# Robonaut2.net
KiCad netlist of a schematic drawn in Altium Designer
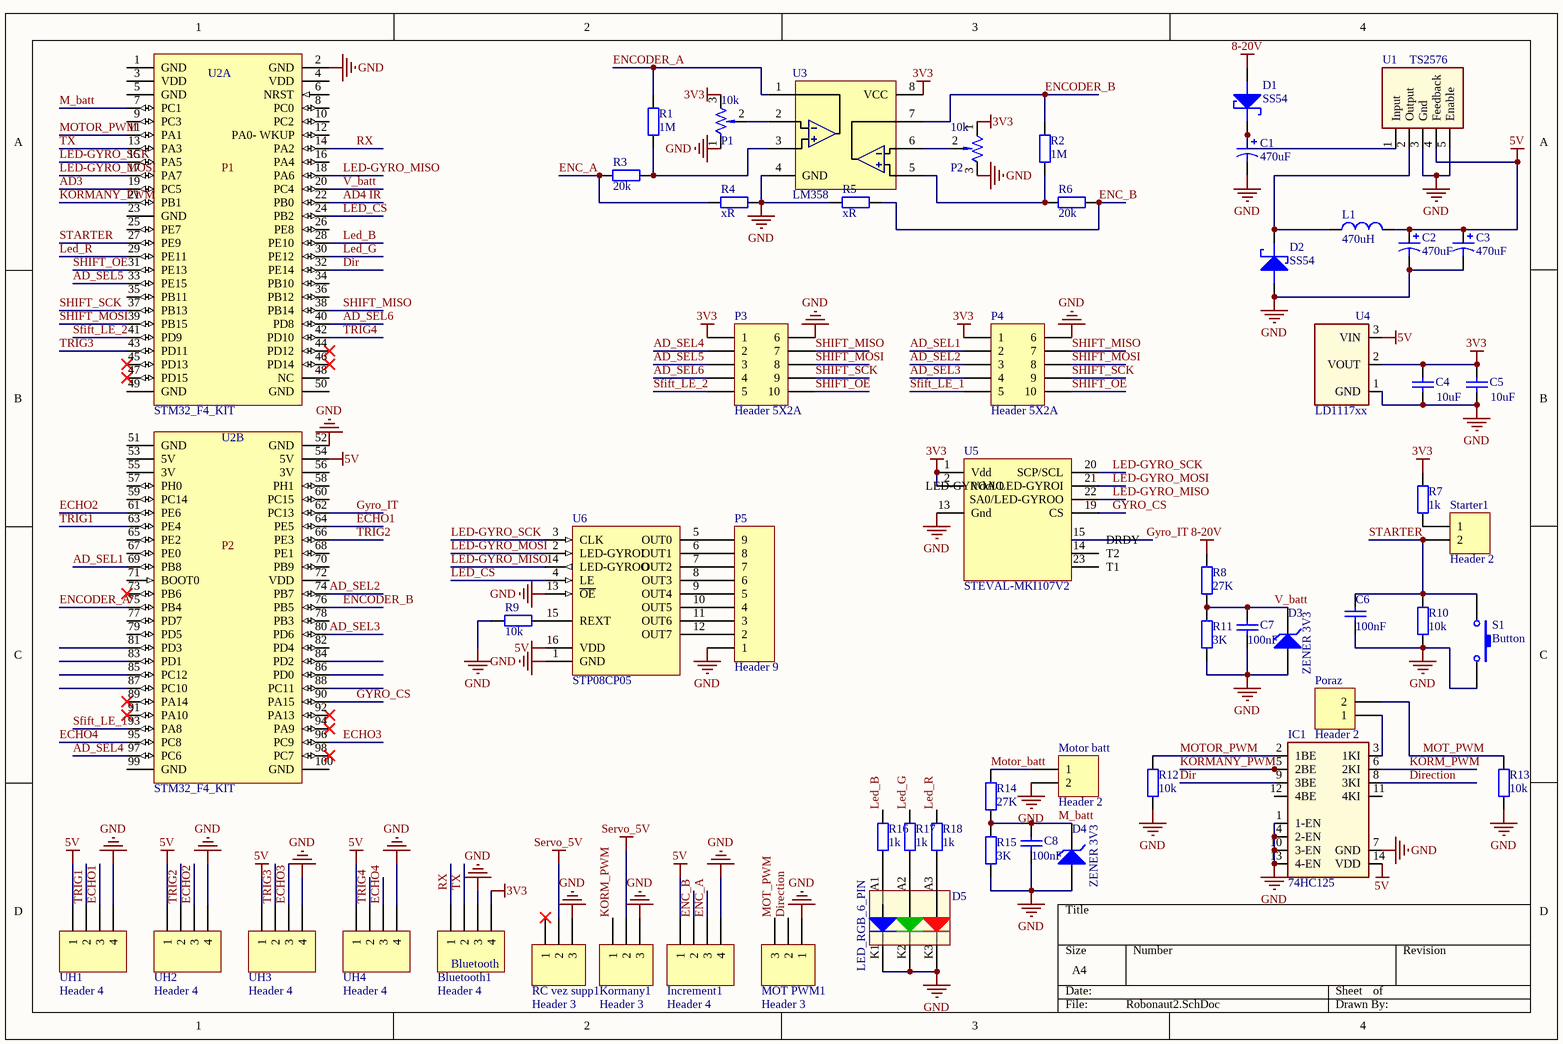
[diagram p0: Robonaut2.SchDoc]

(export (version "E")
  (design (tool "Eeschema 10.0.6"))
  (components
    (comp (ref "Bluetooth1")
      (value "Header 4")
      (footprint "HDR1X4")
      (description "Header, 4-Pin")
      (fields (field (name "PUBLISHER") "Altium Limited"))
      (libsource (lib "Miscellaneous Connectors") (part "Header 4"))
    )
    (comp (ref "C1")
      (value "470uF")
      (footprint "cap_10x12")
      (description "Polarized Capacitor")
      (libsource (lib "Capacitor") (part "CAP_ELECT"))
    )
    (comp (ref "C2")
      (value "470uF")
      (footprint "cap_10x12")
      (description "Polarized Capacitor")
      (libsource (lib "Capacitor") (part "CAP_ELECT"))
    )
    (comp (ref "C3")
      (value "470uF")
      (footprint "cap_10x12")
      (description "Polarized Capacitor")
      (libsource (lib "Capacitor") (part "CAP_ELECT"))
    )
    (comp (ref "C4")
      (value "10uF")
      (footprint "FP_0603_CAP_080")
      (description "Capacitor")
      (fields (field (name "PUBLISHER") "Altium Limited"))
      (libsource (lib "Miscellaneous Devices") (part "Cap"))
    )
    (comp (ref "C5")
      (value "10uF")
      (footprint "FP_0603_CAP_080")
      (description "Capacitor")
      (fields (field (name "PUBLISHER") "Altium Limited"))
      (libsource (lib "Miscellaneous Devices") (part "Cap"))
    )
    (comp (ref "C6")
      (value "100nF")
      (footprint "FP_0805_CAP_085")
      (description "Capacitor")
      (libsource (lib "Capacitor") (part "CAP"))
    )
    (comp (ref "C7")
      (value "100nF")
      (footprint "FP_0805_CAP_085")
      (description "Capacitor")
      (libsource (lib "Capacitor") (part "CAP"))
    )
    (comp (ref "C8")
      (value "100nF")
      (footprint "FP_0805_CAP_085")
      (description "Capacitor")
      (libsource (lib "Capacitor") (part "CAP"))
    )
    (comp (ref "D1")
      (value "SS54")
      (footprint "FP_SMA DO214AB")
      (description "NXP - PMEG3020EJ,115 - SCHOTTKY RECT 30V 2A SOD323F")
      (libsource (lib "Diode") (part "SCHOTTKY"))
    )
    (comp (ref "D2")
      (value "SS54")
      (footprint "FP_SMA DO214AB")
      (description "NXP - PMEG3020EJ,115 - SCHOTTKY RECT 30V 2A SOD323F")
      (libsource (lib "Diode") (part "SCHOTTKY"))
    )
    (comp (ref "D3")
      (value "ZENER 3V3")
      (footprint "sod-80")
      (description "Zener Diode")
      (libsource (lib "Diode") (part "ZENER"))
    )
    (comp (ref "D4")
      (value "ZENER 3V3")
      (footprint "sod-80")
      (description "Zener Diode")
      (libsource (lib "Diode") (part "ZENER"))
    )
    (comp (ref "D5")
      (value "LED_RGB_6_PIN")
      (footprint "LED_PLCC-6")
      (libsource (lib "Led_optical") (part "LED_RGB_6_PIN"))
    )
    (comp (ref "IC1")
      (value "74HC125")
      (footprint "Gate_SOIC14")
      (libsource (lib "Logic_gate") (part "74HC125"))
    )
    (comp (ref "Increment1")
      (value "Header 4")
      (footprint "HDR1X4")
      (description "Header, 4-Pin")
      (fields (field (name "PUBLISHER") "Altium Limited"))
      (libsource (lib "Miscellaneous Connectors") (part "Header 4"))
    )
    (comp (ref "Kormany1")
      (value "Header 3")
      (footprint "HDR1X3")
      (description "Header, 3-Pin")
      (fields (field (name "PUBLISHER") "Altium Limited"))
      (libsource (lib "") (part "Header 3_1"))
    )
    (comp (ref "L1") (value "470uH") (footprint "SRR1206_T") (libsource (lib "Inductor") (part "L")))
    (comp (ref "MOT PWM1")
      (value "Header 3")
      (footprint "HDR1X3")
      (description "Header, 3-Pin")
      (fields (field (name "PUBLISHER") "Altium Limited"))
      (libsource (lib "Miscellaneous Connectors") (part "Header 3"))
    )
    (comp (ref "Motor batt")
      (value "Header 2")
      (footprint "HDR1X2")
      (description "Header, 2-Pin")
      (fields (field (name "PUBLISHER") "Altium Limited"))
      (libsource (lib "Miscellaneous Connectors") (part "Header 2"))
    )
    (comp (ref "P1") (value "10k") (footprint "Res Trimmer TH") (libsource (lib "Resistor") (part "POTI")))
    (comp (ref "P2") (value "10k") (footprint "Res Trimmer TH") (libsource (lib "Resistor") (part "POTI")))
    (comp (ref "P3")
      (value "Header 5X2A")
      (footprint "HDR2X5_CEN")
      (description "Header, 5-Pin, Dual row")
      (fields (field (name "PUBLISHER") "Altium Limited"))
      (libsource (lib "Miscellaneous Connectors") (part "Header 5X2A"))
    )
    (comp (ref "P4")
      (value "Header 5X2A")
      (footprint "HDR2X5_CEN")
      (description "Header, 5-Pin, Dual row")
      (fields (field (name "PUBLISHER") "Altium Limited"))
      (libsource (lib "Miscellaneous Connectors") (part "Header 5X2A"))
    )
    (comp (ref "P5")
      (value "Header 9")
      (footprint "HDR1X9")
      (description "Header, 9-Pin")
      (fields (field (name "PUBLISHER") "Altium Limited"))
      (libsource (lib "Miscellaneous Connectors") (part "Header 9"))
    )
    (comp (ref "Poraz")
      (value "Header 2")
      (footprint "HDR1X2")
      (description "Header, 2-Pin")
      (fields (field (name "PUBLISHER") "Altium Limited"))
      (libsource (lib "") (part "Header 2_1"))
    )
    (comp (ref "R1")
      (value "1M")
      (footprint "FP_0805_RES")
      (description "Resistor")
      (libsource (lib "Resistor") (part "RES"))
    )
    (comp (ref "R2")
      (value "1M")
      (footprint "FP_0805_RES")
      (description "Resistor")
      (libsource (lib "Resistor") (part "RES"))
    )
    (comp (ref "R3")
      (value "20k")
      (footprint "FP_0805_RES")
      (description "Resistor")
      (libsource (lib "") (part "RES_2"))
    )
    (comp (ref "R4")
      (value "xR")
      (footprint "FP_0805_RES")
      (description "Resistor")
      (libsource (lib "") (part "RES_2"))
    )
    (comp (ref "R5")
      (value "xR")
      (footprint "FP_0805_RES")
      (description "Resistor")
      (libsource (lib "") (part "RES_2"))
    )
    (comp (ref "R6")
      (value "20k")
      (footprint "FP_0805_RES")
      (description "Resistor")
      (libsource (lib "") (part "RES_2"))
    )
    (comp (ref "R7")
      (value "1k")
      (footprint "FP_0805_RES")
      (description "Resistor")
      (libsource (lib "Resistor") (part "RES"))
    )
    (comp (ref "R8")
      (value "27K")
      (footprint "FP_0805_RES")
      (description "Resistor")
      (libsource (lib "") (part "RES_1"))
    )
    (comp (ref "R9")
      (value "10k")
      (footprint "FP_0805_RES")
      (description "Resistor")
      (libsource (lib "") (part "RES_3"))
    )
    (comp (ref "R10")
      (value "10k")
      (footprint "FP_0805_RES")
      (description "Resistor")
      (libsource (lib "Resistor") (part "RES"))
    )
    (comp (ref "R11")
      (value "3K")
      (footprint "FP_0805_RES")
      (description "Resistor")
      (libsource (lib "") (part "RES_1"))
    )
    (comp (ref "R12")
      (value "10k")
      (footprint "FP_0805_RES")
      (description "Resistor")
      (libsource (lib "Resistor") (part "RES"))
    )
    (comp (ref "R13")
      (value "10k")
      (footprint "FP_0805_RES")
      (description "Resistor")
      (libsource (lib "") (part "RES_1"))
    )
    (comp (ref "R14")
      (value "27K")
      (footprint "FP_0805_RES")
      (description "Resistor")
      (libsource (lib "") (part "RES_1"))
    )
    (comp (ref "R15")
      (value "3K")
      (footprint "FP_0805_RES")
      (description "Resistor")
      (libsource (lib "") (part "RES_1"))
    )
    (comp (ref "R16")
      (value "1k")
      (footprint "FP_0805_RES")
      (description "Resistor")
      (libsource (lib "Resistor") (part "RES"))
    )
    (comp (ref "R17")
      (value "1k")
      (footprint "FP_0805_RES")
      (description "Resistor")
      (libsource (lib "Resistor") (part "RES"))
    )
    (comp (ref "R18")
      (value "1k")
      (footprint "FP_0805_RES")
      (description "Resistor")
      (libsource (lib "Resistor") (part "RES"))
    )
    (comp (ref "RC vez supp1")
      (value "Header 3")
      (footprint "HDR1X3")
      (description "Header, 3-Pin")
      (fields (field (name "PUBLISHER") "Altium Limited"))
      (libsource (lib "") (part "Header 3_1"))
    )
    (comp (ref "S1")
      (value "Button")
      (footprint "BUTTON_6X6 _SMD")
      (description "Switch")
      (fields (field (name "PUBLISHER") "Altium Limited"))
      (libsource (lib "Miscellaneous Devices") (part "SW-PB"))
    )
    (comp (ref "Starter1")
      (value "Header 2")
      (footprint "HDR1X2")
      (description "Header, 2-Pin")
      (fields (field (name "PUBLISHER") "Altium Limited"))
      (libsource (lib "Miscellaneous Connectors") (part "Header 2"))
    )
    (comp (ref "U1")
      (value "TS2576")
      (footprint "SUPPLY_TO-263 5")
      (description "5V 3A step down")
      (libsource (lib "Supply") (part "TS2576"))
    )
    (comp (ref "U2")
      (value "STM32_F4_KIT")
      (footprint "FP_STM32F4DISC")
      (description "STM32 F4 Discovery Evaluation Kit")
      (libsource (lib "Modul") (part "STM32F4DISCOVERY"))
    )
    (comp (ref "U3")
      (value "LM358")
      (footprint "FP_SO8_MS012AA")
      (description "Low power dual operational amplifiers")
      (libsource (lib "Analog") (part "LM358"))
    )
    (comp (ref "U4")
      (value "LD1117xx")
      (footprint "SUPPLY_SOT223")
      (description "LD1117xx 3,3V lin reg")
      (libsource (lib "Supply") (part "LD1117xx"))
    )
    (comp (ref "U5")
      (value "STEVAL-MKI107V2")
      (footprint "STEVAL-MKI107V2 DIL24 Adapter")
      (description "Three-axis digital output gyroscope")
      (fields (field (name "MANUFACTURER") "STMicroelectronic"))
      (libsource (lib "Modul") (part "STEVAL-MKI107V2"))
    )
    (comp (ref "U6")
      (value "STP08CP05")
      (footprint "TSSOP16")
      (description "8 channel constant current LED driver")
      (fields (field (name "MANUFACTURER") "STMicroelectronic"))
      (libsource (lib "nem rendezett") (part "STP08CP05"))
    )
    (comp (ref "UH1")
      (value "Header 4")
      (footprint "HDR1X4")
      (description "Header, 4-Pin")
      (fields (field (name "PUBLISHER") "Altium Limited"))
      (libsource (lib "Miscellaneous Connectors") (part "Header 4"))
    )
    (comp (ref "UH2")
      (value "Header 4")
      (footprint "HDR1X4")
      (description "Header, 4-Pin")
      (fields (field (name "PUBLISHER") "Altium Limited"))
      (libsource (lib "Miscellaneous Connectors") (part "Header 4"))
    )
    (comp (ref "UH3")
      (value "Header 4")
      (footprint "HDR1X4")
      (description "Header, 4-Pin")
      (fields (field (name "PUBLISHER") "Altium Limited"))
      (libsource (lib "Miscellaneous Connectors") (part "Header 4"))
    )
    (comp (ref "UH4")
      (value "Header 4")
      (footprint "HDR1X4")
      (description "Header, 4-Pin")
      (fields (field (name "PUBLISHER") "Altium Limited"))
      (libsource (lib "Miscellaneous Connectors") (part "Header 4"))
    )
  )
  (nets
    (net (code "1") (name "/AD3") (class "Default")
      (node (ref "U2") (pin "19") (pinfunction "PC5_19") (pintype "bidirectional"))
    )
    (net (code "2") (name "/AD4 IR") (class "Default")
      (node (ref "U2") (pin "22") (pinfunction "PB0_22") (pintype "bidirectional"))
    )
    (net (code "3") (name "/AD_SEL1") (class "Default")
      (node (ref "P4") (pin "2") (pinfunction "2_2") (pintype "passive"))
      (node (ref "U2") (pin "69") (pinfunction "PB8_69") (pintype "bidirectional"))
    )
    (net (code "4") (name "/AD_SEL2") (class "Default")
      (node (ref "P4") (pin "3") (pinfunction "3_3") (pintype "passive"))
      (node (ref "U2") (pin "74") (pinfunction "PB7_74") (pintype "bidirectional"))
    )
    (net (code "5") (name "/AD_SEL3") (class "Default")
      (node (ref "P4") (pin "4") (pinfunction "4_4") (pintype "passive"))
      (node (ref "U2") (pin "80") (pinfunction "PD6_80") (pintype "bidirectional"))
    )
    (net (code "6") (name "/AD_SEL4") (class "Default")
      (node (ref "P3") (pin "2") (pinfunction "2_2") (pintype "passive"))
      (node (ref "U2") (pin "97") (pinfunction "PC6_97") (pintype "bidirectional"))
    )
    (net (code "7") (name "/AD_SEL5") (class "Default")
      (node (ref "P3") (pin "3") (pinfunction "3_3") (pintype "passive"))
      (node (ref "U2") (pin "33") (pinfunction "PE15_33") (pintype "bidirectional"))
    )
    (net (code "8") (name "/AD_SEL6") (class "Default")
      (node (ref "P3") (pin "4") (pinfunction "4_4") (pintype "passive"))
      (node (ref "U2") (pin "40") (pinfunction "PD8_40") (pintype "bidirectional"))
    )
    (net (code "9") (name "/Dir") (class "Default")
      (node (ref "IC1") (pin "9") (pinfunction "3BE_9") (pintype "passive"))
      (node (ref "U2") (pin "32") (pinfunction "PE14_32") (pintype "bidirectional"))
    )
    (net (code "10") (name "/Direction") (class "Default")
      (node (ref "IC1") (pin "8") (pinfunction "3KI_8") (pintype "passive"))
      (node (ref "MOT PWM1") (pin "2") (pinfunction "2_2") (pintype "passive"))
    )
    (net (code "11") (name "/ECHO1") (class "Default")
      (node (ref "U2") (pin "64") (pinfunction "PE5_64") (pintype "bidirectional"))
      (node (ref "UH1") (pin "3") (pinfunction "3_3") (pintype "passive"))
    )
    (net (code "12") (name "/ECHO2") (class "Default")
      (node (ref "U2") (pin "61") (pinfunction "PE6_61") (pintype "bidirectional"))
      (node (ref "UH2") (pin "3") (pinfunction "3_3") (pintype "passive"))
    )
    (net (code "13") (name "/ECHO3") (class "Default")
      (node (ref "U2") (pin "96") (pinfunction "PC9_96") (pintype "bidirectional"))
      (node (ref "UH3") (pin "3") (pinfunction "3_3") (pintype "passive"))
    )
    (net (code "14") (name "/ECHO4") (class "Default")
      (node (ref "U2") (pin "95") (pinfunction "PC8_95") (pintype "bidirectional"))
      (node (ref "UH4") (pin "3") (pinfunction "3_3") (pintype "passive"))
    )
    (net (code "15") (name "/ENCODER_A") (class "Default")
      (node (ref "R1") (pin "2") (pinfunction "2_2") (pintype "passive"))
      (node (ref "U2") (pin "75") (pinfunction "PB4_75") (pintype "bidirectional"))
      (node (ref "U3") (pin "1") (pintype "passive"))
    )
    (net (code "16") (name "/ENCODER_B") (class "Default")
      (node (ref "R2") (pin "2") (pinfunction "2_2") (pintype "passive"))
      (node (ref "U2") (pin "76") (pinfunction "PB5_76") (pintype "bidirectional"))
      (node (ref "U3") (pin "7") (pintype "passive"))
    )
    (net (code "17") (name "/ENC_A") (class "Default")
      (node (ref "Increment1") (pin "3") (pinfunction "3_3") (pintype "passive"))
      (node (ref "R3") (pin "1") (pinfunction "1_1") (pintype "passive"))
      (node (ref "R4") (pin "1") (pinfunction "1_1") (pintype "passive"))
    )
    (net (code "18") (name "/ENC_B") (class "Default")
      (node (ref "Increment1") (pin "2") (pinfunction "2_2") (pintype "passive"))
      (node (ref "R5") (pin "2") (pinfunction "2_2") (pintype "passive"))
      (node (ref "R6") (pin "2") (pinfunction "2_2") (pintype "passive"))
    )
    (net (code "19") (name "/GYRO_CS") (class "Default")
      (node (ref "U2") (pin "90") (pinfunction "PA15_90") (pintype "bidirectional"))
      (node (ref "U5") (pin "19") (pinfunction "CS_19") (pintype "passive"))
    )
    (net (code "20") (name "/Gyro_IT") (class "Default")
      (node (ref "U2") (pin "62") (pinfunction "PC13_62") (pintype "bidirectional"))
      (node (ref "U5") (pin "15") (pinfunction "DRDY_15") (pintype "passive"))
    )
    (net (code "21") (name "/KORMANY_PWM") (class "Default")
      (node (ref "IC1") (pin "5") (pinfunction "2BE_5") (pintype "passive"))
      (node (ref "U2") (pin "21") (pinfunction "PB1_21") (pintype "bidirectional"))
    )
    (net (code "22") (name "/KORM_PWM") (class "Default")
      (node (ref "IC1") (pin "6") (pinfunction "2KI_6") (pintype "passive"))
      (node (ref "Kormany1") (pin "1") (pinfunction "1_1") (pintype "passive"))
    )
    (net (code "23") (name "/LED-GYRO_MISO") (class "Default")
      (node (ref "U2") (pin "18") (pinfunction "PA6_18") (pintype "bidirectional"))
      (node (ref "U5") (pin "22") (pinfunction "SA0/LED-GYROO_22") (pintype "passive"))
      (node (ref "U6") (pin "14") (pinfunction "LED-GYROO_14") (pintype "output"))
    )
    (net (code "24") (name "/LED-GYRO_MOSI") (class "Default")
      (node (ref "U2") (pin "17") (pinfunction "PA7_17") (pintype "bidirectional"))
      (node (ref "U5") (pin "21") (pinfunction "LED-GYROA/LED-GYROI_21") (pintype "passive"))
      (node (ref "U6") (pin "2") (pinfunction "LED-GYROI_2") (pintype "input"))
    )
    (net (code "25") (name "/LED-GYRO_SCK") (class "Default")
      (node (ref "U2") (pin "15") (pinfunction "PA5_15") (pintype "bidirectional"))
      (node (ref "U5") (pin "20") (pinfunction "SCP/SCL_20") (pintype "passive"))
      (node (ref "U6") (pin "3") (pinfunction "CLK_3") (pintype "input"))
    )
    (net (code "26") (name "/LED_CS") (class "Default")
      (node (ref "U2") (pin "24") (pinfunction "PB2_24") (pintype "bidirectional"))
      (node (ref "U6") (pin "4") (pinfunction "LE_4") (pintype "input"))
    )
    (net (code "27") (name "/Led_B") (class "Default")
      (node (ref "R16") (pin "2") (pinfunction "2_2") (pintype "passive"))
      (node (ref "U2") (pin "28") (pinfunction "PE10_28") (pintype "bidirectional"))
    )
    (net (code "28") (name "/Led_G") (class "Default")
      (node (ref "R17") (pin "2") (pinfunction "2_2") (pintype "passive"))
      (node (ref "U2") (pin "30") (pinfunction "PE12_30") (pintype "bidirectional"))
    )
    (net (code "29") (name "/Led_R") (class "Default")
      (node (ref "R18") (pin "2") (pinfunction "2_2") (pintype "passive"))
      (node (ref "U2") (pin "29") (pinfunction "PE11_29") (pintype "bidirectional"))
    )
    (net (code "30") (name "/MOTOR_PWM") (class "Default")
      (node (ref "IC1") (pin "2") (pinfunction "1BE_2") (pintype "passive"))
      (node (ref "R12") (pin "2") (pinfunction "2_2") (pintype "passive"))
      (node (ref "U2") (pin "11") (pinfunction "PA1_11") (pintype "bidirectional"))
    )
    (net (code "31") (name "/MOT_PWM") (class "Default")
      (node (ref "MOT PWM1") (pin "3") (pinfunction "3_3") (pintype "passive"))
      (node (ref "Poraz") (pin "2") (pinfunction "2_2") (pintype "passive"))
      (node (ref "R13") (pin "1") (pinfunction "1_1") (pintype "passive"))
    )
    (net (code "32") (name "/M_batt") (class "Default")
      (node (ref "C8") (pin "2") (pinfunction "2_2") (pintype "passive"))
      (node (ref "D4") (pin "K") (pinfunction "K_K") (pintype "passive"))
      (node (ref "R14") (pin "2") (pinfunction "2_2") (pintype "passive"))
      (node (ref "R15") (pin "1") (pinfunction "1_1") (pintype "passive"))
      (node (ref "U2") (pin "7") (pinfunction "PC1_7") (pintype "bidirectional"))
    )
    (net (code "33") (name "/Motor_batt") (class "Default")
      (node (ref "Motor batt") (pin "1") (pinfunction "1_1") (pintype "passive"))
      (node (ref "R14") (pin "1") (pinfunction "1_1") (pintype "passive"))
    )
    (net (code "34") (name "/RX") (class "Default")
      (node (ref "Bluetooth1") (pin "1") (pinfunction "1_1") (pintype "passive"))
      (node (ref "U2") (pin "14") (pinfunction "PA2_14") (pintype "bidirectional"))
    )
    (net (code "35") (name "/SHIFT_MISO") (class "Default")
      (node (ref "P3") (pin "7") (pinfunction "7_7") (pintype "passive"))
      (node (ref "P4") (pin "7") (pinfunction "7_7") (pintype "passive"))
      (node (ref "U2") (pin "38") (pinfunction "PB14_38") (pintype "bidirectional"))
    )
    (net (code "36") (name "/SHIFT_MOSI") (class "Default")
      (node (ref "P3") (pin "8") (pinfunction "8_8") (pintype "passive"))
      (node (ref "P4") (pin "8") (pinfunction "8_8") (pintype "passive"))
      (node (ref "U2") (pin "39") (pinfunction "PB15_39") (pintype "bidirectional"))
    )
    (net (code "37") (name "/SHIFT_OE") (class "Default")
      (node (ref "P3") (pin "10") (pinfunction "10_10") (pintype "passive"))
      (node (ref "P4") (pin "10") (pinfunction "10_10") (pintype "passive"))
      (node (ref "U2") (pin "31") (pinfunction "PE13_31") (pintype "bidirectional"))
    )
    (net (code "38") (name "/SHIFT_SCK") (class "Default")
      (node (ref "P3") (pin "9") (pinfunction "9_9") (pintype "passive"))
      (node (ref "P4") (pin "9") (pinfunction "9_9") (pintype "passive"))
      (node (ref "U2") (pin "37") (pinfunction "PB13_37") (pintype "bidirectional"))
    )
    (net (code "39") (name "/STARTER") (class "Default")
      (node (ref "C6") (pin "2") (pinfunction "2_2") (pintype "passive"))
      (node (ref "R10") (pin "2") (pinfunction "2_2") (pintype "passive"))
      (node (ref "S1") (pin "1") (pinfunction "1_1") (pintype "passive"))
      (node (ref "Starter1") (pin "2") (pinfunction "2_2") (pintype "passive"))
      (node (ref "U2") (pin "27") (pinfunction "PE9_27") (pintype "bidirectional"))
    )
    (net (code "40") (name "/Sfift_LE_1") (class "Default")
      (node (ref "P4") (pin "5") (pinfunction "5_5") (pintype "passive"))
      (node (ref "U2") (pin "93") (pinfunction "PA8_93") (pintype "bidirectional"))
    )
    (net (code "41") (name "/Sfift_LE_2") (class "Default")
      (node (ref "P3") (pin "5") (pinfunction "5_5") (pintype "passive"))
      (node (ref "U2") (pin "41") (pinfunction "PD9_41") (pintype "bidirectional"))
    )
    (net (code "42") (name "/TRIG1") (class "Default")
      (node (ref "U2") (pin "63") (pinfunction "PE4_63") (pintype "bidirectional"))
      (node (ref "UH1") (pin "2") (pinfunction "2_2") (pintype "passive"))
    )
    (net (code "43") (name "/TRIG2") (class "Default")
      (node (ref "U2") (pin "66") (pinfunction "PE3_66") (pintype "bidirectional"))
      (node (ref "UH2") (pin "2") (pinfunction "2_2") (pintype "passive"))
    )
    (net (code "44") (name "/TRIG3") (class "Default")
      (node (ref "U2") (pin "43") (pinfunction "PD11_43") (pintype "bidirectional"))
      (node (ref "UH3") (pin "2") (pinfunction "2_2") (pintype "passive"))
    )
    (net (code "45") (name "/TRIG4") (class "Default")
      (node (ref "U2") (pin "42") (pinfunction "PD10_42") (pintype "bidirectional"))
      (node (ref "UH4") (pin "2") (pinfunction "2_2") (pintype "passive"))
    )
    (net (code "46") (name "/TX") (class "Default")
      (node (ref "Bluetooth1") (pin "2") (pinfunction "2_2") (pintype "passive"))
      (node (ref "U2") (pin "13") (pinfunction "PA3_13") (pintype "bidirectional"))
    )
    (net (code "47") (name "/V_batt") (class "Default")
      (node (ref "C7") (pin "2") (pinfunction "2_2") (pintype "passive"))
      (node (ref "D3") (pin "K") (pinfunction "K_K") (pintype "passive"))
      (node (ref "R11") (pin "1") (pinfunction "1_1") (pintype "passive"))
      (node (ref "R8") (pin "2") (pinfunction "2_2") (pintype "passive"))
      (node (ref "U2") (pin "20") (pinfunction "PC4_20") (pintype "bidirectional"))
    )
    (net (code "48") (name "3V3") (class "Default")
      (node (ref "Bluetooth1") (pin "4") (pinfunction "4_4") (pintype "passive"))
      (node (ref "C4") (pin "2") (pinfunction "2_2") (pintype "passive"))
      (node (ref "C5") (pin "2") (pinfunction "2_2") (pintype "passive"))
      (node (ref "P1") (pin "3") (pinfunction "2_3") (pintype "passive"))
      (node (ref "P2") (pin "1") (pinfunction "1_1") (pintype "passive"))
      (node (ref "P3") (pin "1") (pinfunction "1_1") (pintype "passive"))
      (node (ref "P4") (pin "1") (pinfunction "1_1") (pintype "passive"))
      (node (ref "R7") (pin "2") (pinfunction "2_2") (pintype "passive"))
      (node (ref "U3") (pin "8") (pinfunction "VCC_8") (pintype "passive"))
      (node (ref "U4") (pin "2") (pinfunction "VOUT_2") (pintype "passive"))
      (node (ref "U5") (pin "1") (pinfunction "Vdd_1") (pintype "power_in"))
      (node (ref "U5") (pin "2") (pinfunction "VddIO_2") (pintype "power_in"))
    )
    (net (code "49") (name "5V") (class "Default")
      (node (ref "C2") (pin "P") (pintype "passive"))
      (node (ref "C3") (pin "P") (pintype "passive"))
      (node (ref "IC1") (pin "14") (pinfunction "VDD_14") (pintype "passive"))
      (node (ref "Increment1") (pin "1") (pinfunction "1_1") (pintype "passive"))
      (node (ref "L1") (pin "2") (pinfunction "2_2") (pintype "passive"))
      (node (ref "U1") (pin "4") (pinfunction "Feedback_4") (pintype "passive"))
      (node (ref "U2") (pin "54") (pinfunction "5V_54") (pintype "power_in"))
      (node (ref "U4") (pin "3") (pinfunction "VIN_3") (pintype "passive"))
      (node (ref "U6") (pin "16") (pinfunction "VDD_16") (pintype "power_in"))
      (node (ref "UH1") (pin "1") (pinfunction "1_1") (pintype "passive"))
      (node (ref "UH2") (pin "1") (pinfunction "1_1") (pintype "passive"))
      (node (ref "UH3") (pin "1") (pinfunction "1_1") (pintype "passive"))
      (node (ref "UH4") (pin "1") (pinfunction "1_1") (pintype "passive"))
    )
    (net (code "50") (name "8-20V") (class "Default")
      (node (ref "D1") (pin "A") (pinfunction "A_A") (pintype "passive"))
      (node (ref "R8") (pin "1") (pinfunction "1_1") (pintype "passive"))
    )
    (net (code "51") (name "GND") (class "Default")
      (node (ref "Bluetooth1") (pin "3") (pinfunction "3_3") (pintype "passive"))
      (node (ref "C1") (pin "N") (pintype "passive"))
      (node (ref "C2") (pin "N") (pintype "passive"))
      (node (ref "C3") (pin "N") (pintype "passive"))
      (node (ref "C4") (pin "1") (pinfunction "1_1") (pintype "passive"))
      (node (ref "C5") (pin "1") (pinfunction "1_1") (pintype "passive"))
      (node (ref "C6") (pin "1") (pinfunction "1_1") (pintype "passive"))
      (node (ref "C7") (pin "1") (pinfunction "1_1") (pintype "passive"))
      (node (ref "C8") (pin "1") (pinfunction "1_1") (pintype "passive"))
      (node (ref "D2") (pin "A") (pinfunction "A_A") (pintype "passive"))
      (node (ref "D3") (pin "A") (pinfunction "A_A") (pintype "passive"))
      (node (ref "D4") (pin "A") (pinfunction "A_A") (pintype "passive"))
      (node (ref "D5") (pin "K1") (pinfunction "R_K1") (pintype "passive"))
      (node (ref "D5") (pin "K2") (pinfunction "G_K2") (pintype "passive"))
      (node (ref "D5") (pin "K3") (pinfunction "B_K3") (pintype "passive"))
      (node (ref "IC1") (pin "1") (pinfunction "1-EN_1") (pintype "passive"))
      (node (ref "IC1") (pin "10") (pinfunction "3-EN_10") (pintype "passive"))
      (node (ref "IC1") (pin "13") (pinfunction "4-EN_13") (pintype "passive"))
      (node (ref "IC1") (pin "4") (pinfunction "2-EN_4") (pintype "passive"))
      (node (ref "IC1") (pin "7") (pinfunction "GND_7") (pintype "passive"))
      (node (ref "Increment1") (pin "4") (pinfunction "4_4") (pintype "passive"))
      (node (ref "Kormany1") (pin "3") (pinfunction "3_3") (pintype "passive"))
      (node (ref "MOT PWM1") (pin "1") (pinfunction "1_1") (pintype "passive"))
      (node (ref "Motor batt") (pin "2") (pinfunction "2_2") (pintype "passive"))
      (node (ref "P1") (pin "1") (pinfunction "1_1") (pintype "passive"))
      (node (ref "P2") (pin "3") (pinfunction "2_3") (pintype "passive"))
      (node (ref "P3") (pin "6") (pinfunction "6_6") (pintype "passive"))
      (node (ref "P4") (pin "6") (pinfunction "6_6") (pintype "passive"))
      (node (ref "P5") (pin "1") (pinfunction "1_1") (pintype "passive"))
      (node (ref "R10") (pin "1") (pinfunction "1_1") (pintype "passive"))
      (node (ref "R11") (pin "2") (pinfunction "2_2") (pintype "passive"))
      (node (ref "R12") (pin "1") (pinfunction "1_1") (pintype "passive"))
      (node (ref "R13") (pin "2") (pinfunction "2_2") (pintype "passive"))
      (node (ref "R15") (pin "2") (pinfunction "2_2") (pintype "passive"))
      (node (ref "R4") (pin "2") (pinfunction "2_2") (pintype "passive"))
      (node (ref "R5") (pin "1") (pinfunction "1_1") (pintype "passive"))
      (node (ref "R9") (pin "2") (pinfunction "2_2") (pintype "passive"))
      (node (ref "RC vez supp1") (pin "3") (pinfunction "3_3") (pintype "passive"))
      (node (ref "S1") (pin "2") (pinfunction "2_2") (pintype "passive"))
      (node (ref "U1") (pin "3") (pinfunction "Gnd_3") (pintype "passive"))
      (node (ref "U1") (pin "5") (pinfunction "Enable_5") (pintype "passive"))
      (node (ref "U2") (pin "2") (pinfunction "GND_2") (pintype "power_in"))
      (node (ref "U2") (pin "52") (pinfunction "GND_52") (pintype "power_in"))
      (node (ref "U3") (pin "4") (pinfunction "GND_4") (pintype "passive"))
      (node (ref "U4") (pin "1") (pinfunction "GND_1") (pintype "passive"))
      (node (ref "U5") (pin "13") (pinfunction "Gnd_13") (pintype "power_in"))
      (node (ref "U6") (pin "1") (pinfunction "GND_1") (pintype "power_in"))
      (node (ref "U6") (pin "13") (pinfunction "~{OE}_13") (pintype "input"))
      (node (ref "UH1") (pin "4") (pinfunction "4_4") (pintype "passive"))
      (node (ref "UH2") (pin "4") (pinfunction "4_4") (pintype "passive"))
      (node (ref "UH3") (pin "4") (pinfunction "4_4") (pintype "passive"))
      (node (ref "UH4") (pin "4") (pinfunction "4_4") (pintype "passive"))
    )
    (net (code "52") (name "Net-(D5-A-PadA1)") (class "Default")
      (node (ref "D5") (pin "A1") (pinfunction "A_A1") (pintype "passive"))
      (node (ref "R16") (pin "1") (pinfunction "1_1") (pintype "passive"))
    )
    (net (code "53") (name "Net-(D5-A-PadA2)") (class "Default")
      (node (ref "D5") (pin "A2") (pinfunction "A_A2") (pintype "passive"))
      (node (ref "R17") (pin "1") (pinfunction "1_1") (pintype "passive"))
    )
    (net (code "54") (name "Net-(D5-A-PadA3)") (class "Default")
      (node (ref "D5") (pin "A3") (pinfunction "A_A3") (pintype "passive"))
      (node (ref "R18") (pin "1") (pinfunction "1_1") (pintype "passive"))
    )
    (net (code "55") (name "Net-(IC1-1KI)") (class "Default")
      (node (ref "IC1") (pin "3") (pinfunction "1KI_3") (pintype "passive"))
      (node (ref "Poraz") (pin "1") (pinfunction "1_1") (pintype "passive"))
    )
    (net (code "56") (name "Net-(P1-t)") (class "Default")
      (node (ref "P1") (pin "2") (pinfunction "t_2") (pintype "passive"))
      (node (ref "U3") (pin "2") (pintype "passive"))
    )
    (net (code "57") (name "Net-(P2-t)") (class "Default")
      (node (ref "P2") (pin "2") (pinfunction "t_2") (pintype "passive"))
      (node (ref "U3") (pin "6") (pintype "passive"))
    )
    (net (code "58") (name "Net-(R1-Pad1)") (class "Default")
      (node (ref "R1") (pin "1") (pinfunction "1_1") (pintype "passive"))
      (node (ref "R3") (pin "2") (pinfunction "2_2") (pintype "passive"))
      (node (ref "U3") (pin "3") (pintype "passive"))
    )
    (net (code "59") (name "Net-(R2-Pad1)") (class "Default")
      (node (ref "R2") (pin "1") (pinfunction "1_1") (pintype "passive"))
      (node (ref "R6") (pin "1") (pinfunction "1_1") (pintype "passive"))
      (node (ref "U3") (pin "5") (pintype "passive"))
    )
    (net (code "60") (name "Net-(R7-Pad1)") (class "Default")
      (node (ref "R7") (pin "1") (pinfunction "1_1") (pintype "passive"))
      (node (ref "Starter1") (pin "1") (pinfunction "1_1") (pintype "passive"))
    )
    (net (code "61") (name "Net-(U1-Input)") (class "Default")
      (node (ref "C1") (pin "P") (pintype "passive"))
      (node (ref "D1") (pin "K") (pinfunction "K_K") (pintype "passive"))
      (node (ref "U1") (pin "1") (pinfunction "Input_1") (pintype "passive"))
    )
    (net (code "62") (name "Net-(U1-Output)") (class "Default")
      (node (ref "D2") (pin "K") (pinfunction "K_K") (pintype "passive"))
      (node (ref "L1") (pin "1") (pinfunction "1_1") (pintype "passive"))
      (node (ref "U1") (pin "2") (pinfunction "Output_2") (pintype "passive"))
    )
    (net (code "63") (name "Net-(U6-OUT0)") (class "Default")
      (node (ref "P5") (pin "9") (pinfunction "9_9") (pintype "passive"))
      (node (ref "U6") (pin "5") (pinfunction "OUT0_5") (pintype "open_collector"))
    )
    (net (code "64") (name "Net-(U6-OUT1)") (class "Default")
      (node (ref "P5") (pin "8") (pinfunction "8_8") (pintype "passive"))
      (node (ref "U6") (pin "6") (pinfunction "OUT1_6") (pintype "open_collector"))
    )
    (net (code "65") (name "Net-(U6-OUT2)") (class "Default")
      (node (ref "P5") (pin "7") (pinfunction "7_7") (pintype "passive"))
      (node (ref "U6") (pin "7") (pinfunction "OUT2_7") (pintype "open_collector"))
    )
    (net (code "66") (name "Net-(U6-OUT3)") (class "Default")
      (node (ref "P5") (pin "6") (pinfunction "6_6") (pintype "passive"))
      (node (ref "U6") (pin "8") (pinfunction "OUT3_8") (pintype "open_collector"))
    )
    (net (code "67") (name "Net-(U6-OUT4)") (class "Default")
      (node (ref "P5") (pin "5") (pinfunction "5_5") (pintype "passive"))
      (node (ref "U6") (pin "9") (pinfunction "OUT4_9") (pintype "open_collector"))
    )
    (net (code "68") (name "Net-(U6-OUT5)") (class "Default")
      (node (ref "P5") (pin "4") (pinfunction "4_4") (pintype "passive"))
      (node (ref "U6") (pin "10") (pinfunction "OUT5_10") (pintype "open_collector"))
    )
    (net (code "69") (name "Net-(U6-OUT6)") (class "Default")
      (node (ref "P5") (pin "3") (pinfunction "3_3") (pintype "passive"))
      (node (ref "U6") (pin "11") (pinfunction "OUT6_11") (pintype "open_collector"))
    )
    (net (code "70") (name "Net-(U6-OUT7)") (class "Default")
      (node (ref "P5") (pin "2") (pinfunction "2_2") (pintype "passive"))
      (node (ref "U6") (pin "12") (pinfunction "OUT7_12") (pintype "open_collector"))
    )
    (net (code "71") (name "Net-(U6-REXT)") (class "Default")
      (node (ref "R9") (pin "1") (pinfunction "1_1") (pintype "passive"))
      (node (ref "U6") (pin "15") (pinfunction "REXT_15") (pintype "passive"))
    )
    (net (code "72") (name "Servo_5V") (class "Default")
      (node (ref "Kormany1") (pin "2") (pinfunction "2_2") (pintype "passive"))
      (node (ref "RC vez supp1") (pin "2") (pinfunction "2_2") (pintype "passive"))
    )
    (net (code "73") (name "unconnected-(IC1-4BE-Pad12)") (class "Default")
      (node (ref "IC1") (pin "12") (pinfunction "4BE_12") (pintype "passive"))
    )
    (net (code "74") (name "unconnected-(IC1-4KI-Pad11)") (class "Default")
      (node (ref "IC1") (pin "11") (pinfunction "4KI_11") (pintype "passive"))
    )
    (net (code "75") (name "unconnected-(RC vez supp1-Pad1)") (class "Default")
      (node (ref "RC vez supp1") (pin "1") (pinfunction "1_1") (pintype "passive+no_connect"))
    )
    (net (code "76") (name "unconnected-(U2A-GND-Pad1)") (class "Default")
      (node (ref "U2") (pin "1") (pinfunction "GND_1") (pintype "power_in"))
    )
    (net (code "77") (name "unconnected-(U2A-GND-Pad5)") (class "Default")
      (node (ref "U2") (pin "5") (pinfunction "GND_5") (pintype "power_in"))
    )
    (net (code "78") (name "unconnected-(U2A-GND-Pad23)") (class "Default")
      (node (ref "U2") (pin "23") (pinfunction "GND_23") (pintype "power_in"))
    )
    (net (code "79") (name "unconnected-(U2A-GND-Pad49)") (class "Default")
      (node (ref "U2") (pin "49") (pinfunction "GND_49") (pintype "power_in"))
    )
    (net (code "80") (name "unconnected-(U2A-GND-Pad50)") (class "Default")
      (node (ref "U2") (pin "50") (pinfunction "GND_50") (pintype "power_in"))
    )
    (net (code "81") (name "unconnected-(U2A-NC-Pad48)") (class "Default")
      (node (ref "U2") (pin "48") (pinfunction "NC_48") (pintype "passive"))
    )
    (net (code "82") (name "unconnected-(U2A-NRST-Pad6)") (class "Default")
      (node (ref "U2") (pin "6") (pinfunction "NRST_6") (pintype "input"))
    )
    (net (code "83") (name "unconnected-(U2A-PA0-_WKUP-Pad12)") (class "Default")
      (node (ref "U2") (pin "12") (pinfunction "PA0-_WKUP_12") (pintype "bidirectional"))
    )
    (net (code "84") (name "unconnected-(U2A-PA4-Pad16)") (class "Default")
      (node (ref "U2") (pin "16") (pinfunction "PA4_16") (pintype "bidirectional"))
    )
    (net (code "85") (name "unconnected-(U2A-PB10-Pad34)") (class "Default")
      (node (ref "U2") (pin "34") (pinfunction "PB10_34") (pintype "bidirectional"))
    )
    (net (code "86") (name "unconnected-(U2A-PB11-Pad35)") (class "Default")
      (node (ref "U2") (pin "35") (pinfunction "PB11_35") (pintype "bidirectional"))
    )
    (net (code "87") (name "unconnected-(U2A-PB12-Pad36)") (class "Default")
      (node (ref "U2") (pin "36") (pinfunction "PB12_36") (pintype "bidirectional"))
    )
    (net (code "88") (name "unconnected-(U2A-PC0-Pad8)") (class "Default")
      (node (ref "U2") (pin "8") (pinfunction "PC0_8") (pintype "bidirectional"))
    )
    (net (code "89") (name "unconnected-(U2A-PC2-Pad10)") (class "Default")
      (node (ref "U2") (pin "10") (pinfunction "PC2_10") (pintype "bidirectional"))
    )
    (net (code "90") (name "unconnected-(U2A-PC3-Pad9)") (class "Default")
      (node (ref "U2") (pin "9") (pinfunction "PC3_9") (pintype "bidirectional"))
    )
    (net (code "91") (name "unconnected-(U2A-PD12-Pad44)") (class "Default")
      (node (ref "U2") (pin "44") (pinfunction "PD12_44") (pintype "bidirectional+no_connect"))
    )
    (net (code "92") (name "unconnected-(U2A-PD13-Pad45)") (class "Default")
      (node (ref "U2") (pin "45") (pinfunction "PD13_45") (pintype "bidirectional+no_connect"))
    )
    (net (code "93") (name "unconnected-(U2A-PD14-Pad46)") (class "Default")
      (node (ref "U2") (pin "46") (pinfunction "PD14_46") (pintype "bidirectional+no_connect"))
    )
    (net (code "94") (name "unconnected-(U2A-PD15-Pad47)") (class "Default")
      (node (ref "U2") (pin "47") (pinfunction "PD15_47") (pintype "bidirectional+no_connect"))
    )
    (net (code "95") (name "unconnected-(U2A-PE7-Pad25)") (class "Default")
      (node (ref "U2") (pin "25") (pinfunction "PE7_25") (pintype "bidirectional"))
    )
    (net (code "96") (name "unconnected-(U2A-PE8-Pad26)") (class "Default")
      (node (ref "U2") (pin "26") (pinfunction "PE8_26") (pintype "bidirectional"))
    )
    (net (code "97") (name "unconnected-(U2A-VDD-Pad3)") (class "Default")
      (node (ref "U2") (pin "3") (pinfunction "VDD_3") (pintype "power_in"))
    )
    (net (code "98") (name "unconnected-(U2A-VDD-Pad4)") (class "Default")
      (node (ref "U2") (pin "4") (pinfunction "VDD_4") (pintype "power_in"))
    )
    (net (code "99") (name "unconnected-(U2B-3V-Pad55)") (class "Default")
      (node (ref "U2") (pin "55") (pinfunction "3V_55") (pintype "power_in"))
    )
    (net (code "100") (name "unconnected-(U2B-3V-Pad56)") (class "Default")
      (node (ref "U2") (pin "56") (pinfunction "3V_56") (pintype "power_in"))
    )
    (net (code "101") (name "unconnected-(U2B-5V-Pad53)") (class "Default")
      (node (ref "U2") (pin "53") (pinfunction "5V_53") (pintype "power_in"))
    )
    (net (code "102") (name "unconnected-(U2B-BOOT0-Pad71)") (class "Default")
      (node (ref "U2") (pin "71") (pinfunction "BOOT0_71") (pintype "input"))
    )
    (net (code "103") (name "unconnected-(U2B-GND-Pad51)") (class "Default")
      (node (ref "U2") (pin "51") (pinfunction "GND_51") (pintype "power_in"))
    )
    (net (code "104") (name "unconnected-(U2B-GND-Pad99)") (class "Default")
      (node (ref "U2") (pin "99") (pinfunction "GND_99") (pintype "power_in"))
    )
    (net (code "105") (name "unconnected-(U2B-GND-Pad100)") (class "Default")
      (node (ref "U2") (pin "100") (pinfunction "GND_100") (pintype "power_in"))
    )
    (net (code "106") (name "unconnected-(U2B-PA9-Pad94)") (class "Default")
      (node (ref "U2") (pin "94") (pinfunction "PA9_94") (pintype "bidirectional+no_connect"))
    )
    (net (code "107") (name "unconnected-(U2B-PA10-Pad91)") (class "Default")
      (node (ref "U2") (pin "91") (pinfunction "PA10_91") (pintype "bidirectional+no_connect"))
    )
    (net (code "108") (name "unconnected-(U2B-PA13-Pad92)") (class "Default")
      (node (ref "U2") (pin "92") (pinfunction "PA13_92") (pintype "bidirectional+no_connect"))
    )
    (net (code "109") (name "unconnected-(U2B-PA14-Pad89)") (class "Default")
      (node (ref "U2") (pin "89") (pinfunction "PA14_89") (pintype "bidirectional+no_connect"))
    )
    (net (code "110") (name "unconnected-(U2B-PB3-Pad78)") (class "Default")
      (node (ref "U2") (pin "78") (pinfunction "PB3_78") (pintype "bidirectional"))
    )
    (net (code "111") (name "unconnected-(U2B-PB6-Pad73)") (class "Default")
      (node (ref "U2") (pin "73") (pinfunction "PB6_73") (pintype "bidirectional+no_connect"))
    )
    (net (code "112") (name "unconnected-(U2B-PB9-Pad70)") (class "Default")
      (node (ref "U2") (pin "70") (pinfunction "PB9_70") (pintype "bidirectional"))
    )
    (net (code "113") (name "unconnected-(U2B-PC7-Pad98)") (class "Default")
      (node (ref "U2") (pin "98") (pinfunction "PC7_98") (pintype "bidirectional+no_connect"))
    )
    (net (code "114") (name "unconnected-(U2B-PC10-Pad87)") (class "Default")
      (node (ref "U2") (pin "87") (pinfunction "PC10_87") (pintype "bidirectional"))
    )
    (net (code "115") (name "unconnected-(U2B-PC11-Pad88)") (class "Default")
      (node (ref "U2") (pin "88") (pinfunction "PC11_88") (pintype "bidirectional"))
    )
    (net (code "116") (name "unconnected-(U2B-PC12-Pad85)") (class "Default")
      (node (ref "U2") (pin "85") (pinfunction "PC12_85") (pintype "bidirectional"))
    )
    (net (code "117") (name "unconnected-(U2B-PC14-Pad59)") (class "Default")
      (node (ref "U2") (pin "59") (pinfunction "PC14_59") (pintype "bidirectional"))
    )
    (net (code "118") (name "unconnected-(U2B-PC15-Pad60)") (class "Default")
      (node (ref "U2") (pin "60") (pinfunction "PC15_60") (pintype "bidirectional"))
    )
    (net (code "119") (name "unconnected-(U2B-PD0-Pad86)") (class "Default")
      (node (ref "U2") (pin "86") (pinfunction "PD0_86") (pintype "bidirectional"))
    )
    (net (code "120") (name "unconnected-(U2B-PD1-Pad83)") (class "Default")
      (node (ref "U2") (pin "83") (pinfunction "PD1_83") (pintype "bidirectional"))
    )
    (net (code "121") (name "unconnected-(U2B-PD2-Pad84)") (class "Default")
      (node (ref "U2") (pin "84") (pinfunction "PD2_84") (pintype "bidirectional"))
    )
    (net (code "122") (name "unconnected-(U2B-PD3-Pad81)") (class "Default")
      (node (ref "U2") (pin "81") (pinfunction "PD3_81") (pintype "bidirectional"))
    )
    (net (code "123") (name "unconnected-(U2B-PD4-Pad82)") (class "Default")
      (node (ref "U2") (pin "82") (pinfunction "PD4_82") (pintype "bidirectional"))
    )
    (net (code "124") (name "unconnected-(U2B-PD5-Pad79)") (class "Default")
      (node (ref "U2") (pin "79") (pinfunction "PD5_79") (pintype "bidirectional"))
    )
    (net (code "125") (name "unconnected-(U2B-PD7-Pad77)") (class "Default")
      (node (ref "U2") (pin "77") (pinfunction "PD7_77") (pintype "bidirectional"))
    )
    (net (code "126") (name "unconnected-(U2B-PE0-Pad67)") (class "Default")
      (node (ref "U2") (pin "67") (pinfunction "PE0_67") (pintype "bidirectional"))
    )
    (net (code "127") (name "unconnected-(U2B-PE1-Pad68)") (class "Default")
      (node (ref "U2") (pin "68") (pinfunction "PE1_68") (pintype "bidirectional"))
    )
    (net (code "128") (name "unconnected-(U2B-PE2-Pad65)") (class "Default")
      (node (ref "U2") (pin "65") (pinfunction "PE2_65") (pintype "bidirectional"))
    )
    (net (code "129") (name "unconnected-(U2B-PH0-Pad57)") (class "Default")
      (node (ref "U2") (pin "57") (pinfunction "PH0_57") (pintype "bidirectional"))
    )
    (net (code "130") (name "unconnected-(U2B-PH1-Pad58)") (class "Default")
      (node (ref "U2") (pin "58") (pinfunction "PH1_58") (pintype "bidirectional"))
    )
    (net (code "131") (name "unconnected-(U2B-VDD-Pad72)") (class "Default")
      (node (ref "U2") (pin "72") (pinfunction "VDD_72") (pintype "power_in"))
    )
    (net (code "132") (name "unconnected-(U5-T1-Pad23)") (class "Default")
      (node (ref "U5") (pin "23") (pinfunction "T1_23") (pintype "passive"))
    )
    (net (code "133") (name "unconnected-(U5-T2-Pad14)") (class "Default")
      (node (ref "U5") (pin "14") (pinfunction "T2_14") (pintype "passive"))
    )
  )
)
